# main.net
KiCad netlist of a schematic drawn in Altium Designer
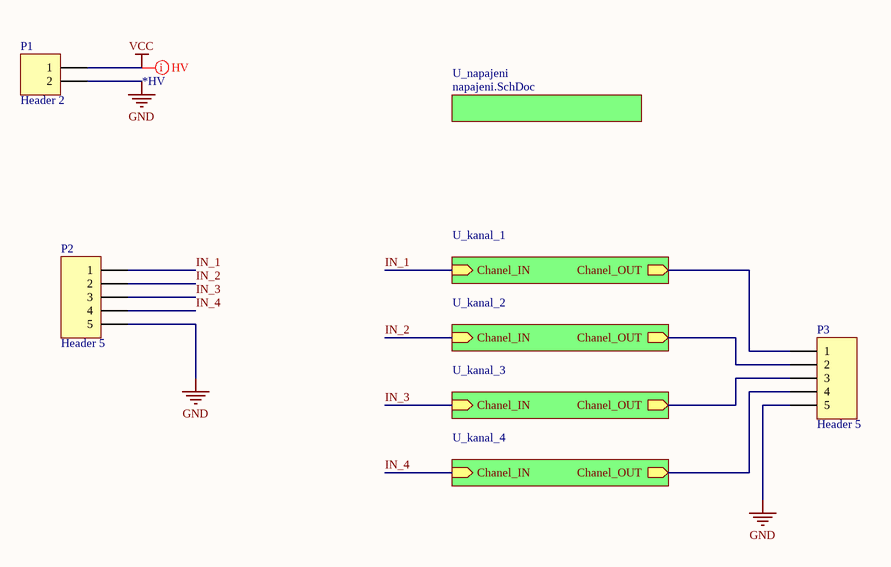
[diagram p0: main.SchDoc]

(export (version "E")
  (design (tool "Eeschema 10.0.6"))
  (components
    (comp (ref "P1")
      (value "Header 2")
      (footprint "HDR1X2")
      (description "Header, 2-Pin")
      (fields (field (name "PUBLISHER") "Altium Limited"))
      (libsource (lib "Miscellaneous Connectors") (part "Header 2"))
    )
    (comp (ref "P2")
      (value "Header 5")
      (footprint "HDR1X5")
      (description "Header, 5-Pin")
      (fields (field (name "PUBLISHER") "Altium Limited"))
      (libsource (lib "Miscellaneous Connectors") (part "Header 5"))
    )
    (comp (ref "P3")
      (value "Header 5")
      (footprint "HDR1X5")
      (description "Header, 5-Pin")
      (fields (field (name "PUBLISHER") "Altium Limited"))
      (libsource (lib "") (part "Header 5_1"))
    )
  )
  (nets
    (net (code "1") (name "/Chanel_OUT") (class "Default")
      (node (ref "P3") (pin "4") (pinfunction "4_4") (pintype "passive"))
    )
    (net (code "2") (name "/Chanel_OUT_1") (class "Default")
      (node (ref "P3") (pin "1") (pinfunction "1_1") (pintype "passive"))
    )
    (net (code "3") (name "/Chanel_OUT_2") (class "Default")
      (node (ref "P3") (pin "2") (pinfunction "2_2") (pintype "passive"))
    )
    (net (code "4") (name "/Chanel_OUT_3") (class "Default")
      (node (ref "P3") (pin "3") (pinfunction "3_3") (pintype "passive"))
    )
    (net (code "5") (name "/IN_1") (class "Default")
      (node (ref "P2") (pin "1") (pinfunction "1_1") (pintype "passive"))
    )
    (net (code "6") (name "/IN_2") (class "Default")
      (node (ref "P2") (pin "2") (pinfunction "2_2") (pintype "passive"))
    )
    (net (code "7") (name "/IN_3") (class "Default")
      (node (ref "P2") (pin "3") (pinfunction "3_3") (pintype "passive"))
    )
    (net (code "8") (name "/IN_4") (class "Default")
      (node (ref "P2") (pin "4") (pinfunction "4_4") (pintype "passive"))
    )
    (net (code "9") (name "GND") (class "Default")
      (node (ref "P1") (pin "2") (pinfunction "2_2") (pintype "passive"))
      (node (ref "P2") (pin "5") (pinfunction "5_5") (pintype "passive"))
      (node (ref "P3") (pin "5") (pinfunction "5_5") (pintype "passive"))
    )
    (net (code "10") (name "VCC") (class "Default")
      (node (ref "P1") (pin "1") (pinfunction "1_1") (pintype "passive"))
    )
  )
)
